# IMU_PCB.net
KiCad netlist of a schematic drawn in EAGLE
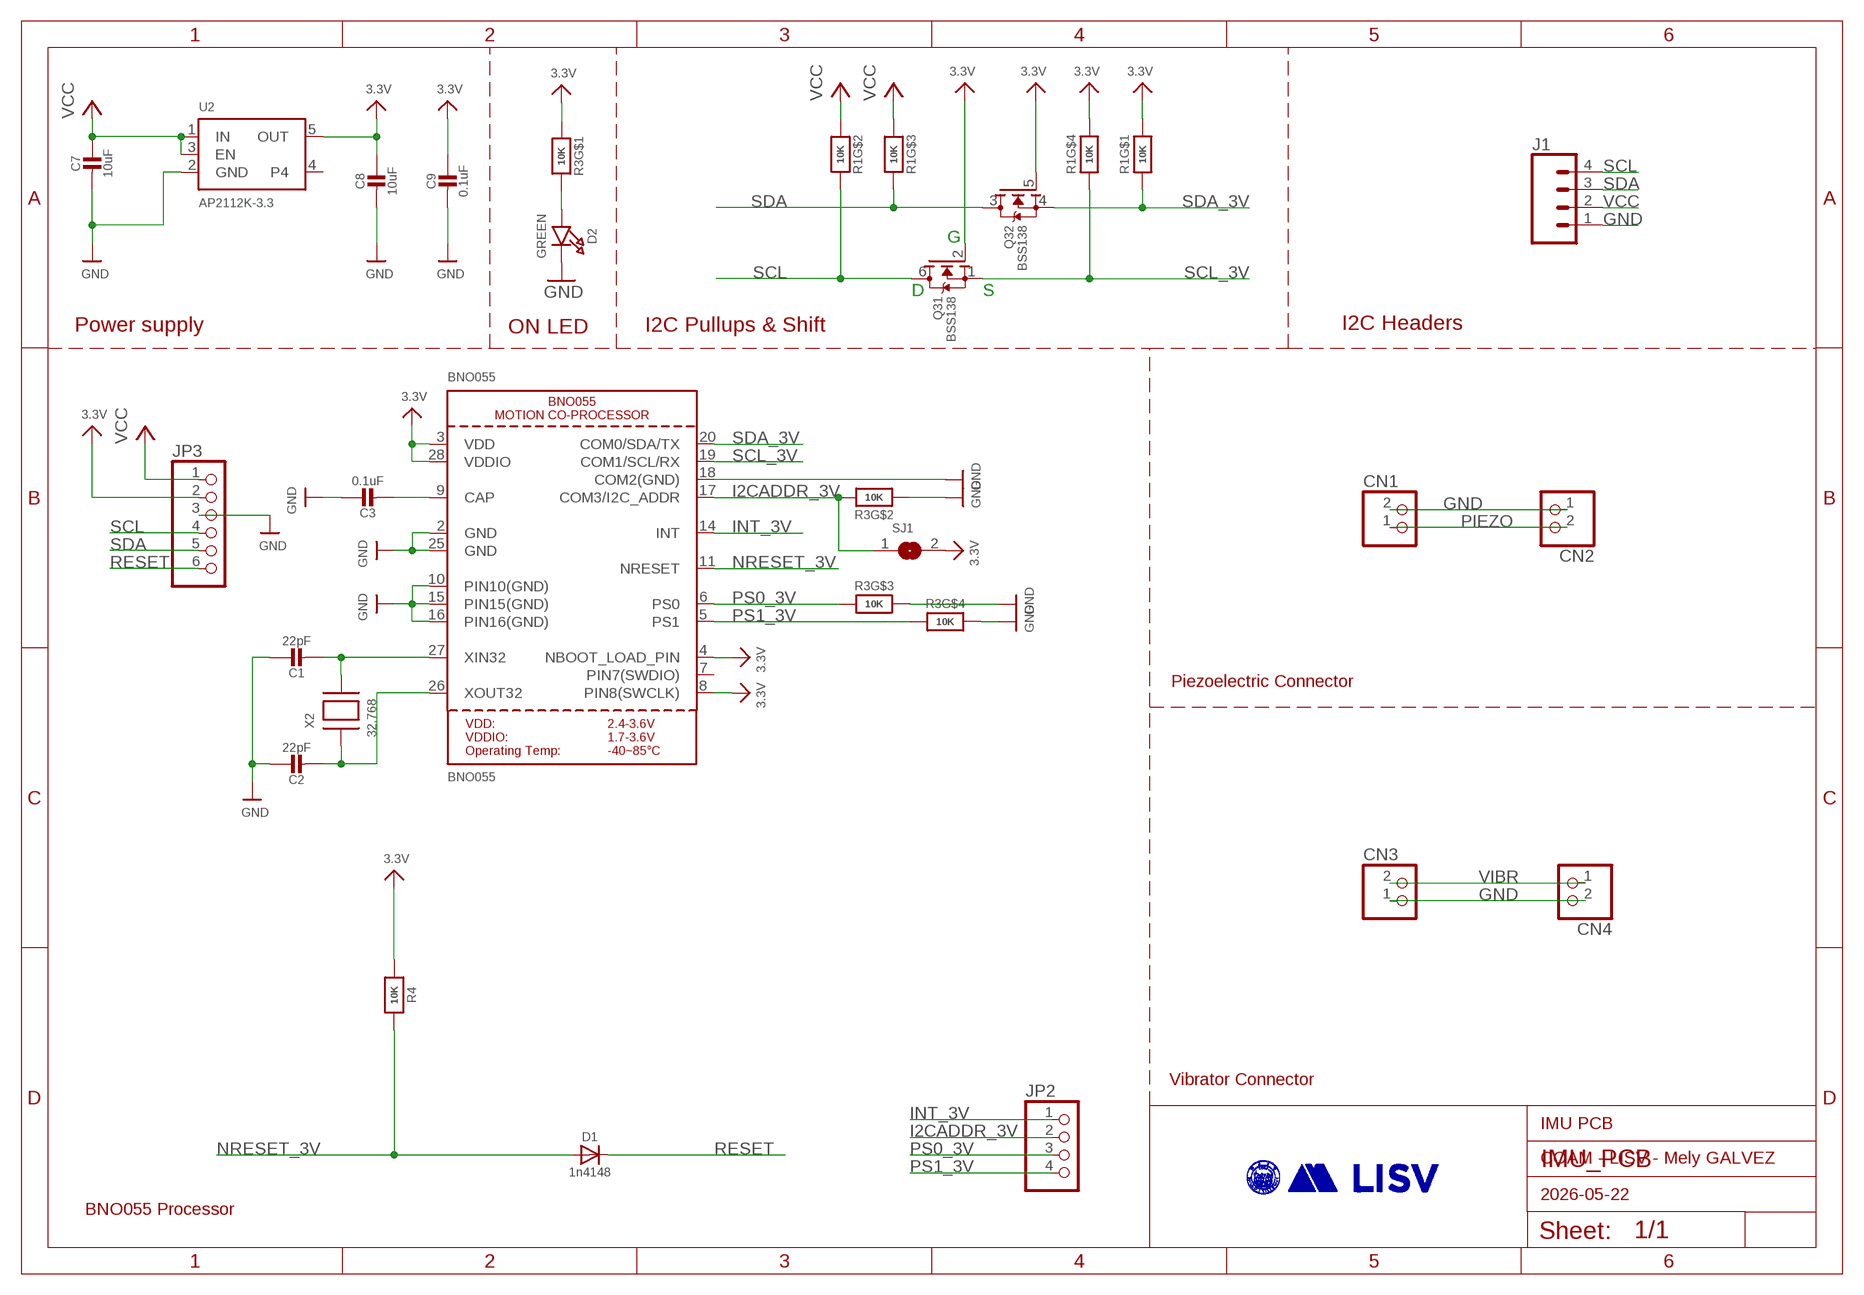
[diagram p0: schematic, sheet 1]

(export (version "E")
  (design (tool "Eeschema 10.0.6"))
  (components
    (comp (ref "BNO055")
      (value "BNO055")
      (footprint "eagle-import:BNO055")
      (libsource (lib "eagle-import") (part "BNO055"))
    )
    (comp (ref "C1")
      (value "22pF")
      (footprint "eagle-import:0603-NO")
      (libsource (lib "eagle-import") (part "CAP_CERAMIC0603_NO"))
    )
    (comp (ref "C2")
      (value "22pF")
      (footprint "eagle-import:0603-NO")
      (libsource (lib "eagle-import") (part "CAP_CERAMIC0603_NO"))
    )
    (comp (ref "C3")
      (value "0.1uF")
      (footprint "eagle-import:0603-NO")
      (libsource (lib "eagle-import") (part "CAP_CERAMIC0603_NO"))
    )
    (comp (ref "C7")
      (value "10uF")
      (footprint "eagle-import:0805-NO")
      (libsource (lib "eagle-import") (part "CAP_CERAMIC0805-NOOUTLINE"))
    )
    (comp (ref "C8")
      (value "10uF")
      (footprint "eagle-import:0805-NO")
      (libsource (lib "eagle-import") (part "CAP_CERAMIC0805-NOOUTLINE"))
    )
    (comp (ref "C9")
      (value "0.1uF")
      (footprint "eagle-import:0603-NO")
      (libsource (lib "eagle-import") (part "CAP_CERAMIC0603_NO"))
    )
    (comp (ref "CN1")
      (value "JST_2PIN-SMT-RA")
      (footprint "eagle-import:JST-PH-2-SMT-RA")
      (libsource (lib "eagle-import") (part "JST_2PIN-SMT-RA"))
    )
    (comp (ref "CN2")
      (value "JST_2PIN-SMT-RA")
      (footprint "eagle-import:JST-PH-2-SMT-RA")
      (libsource (lib "eagle-import") (part "JST_2PIN-SMT-RA"))
    )
    (comp (ref "CN3")
      (value "JST_2PIN-SMT-RA")
      (footprint "eagle-import:JST-PH-2-SMT-RA")
      (libsource (lib "eagle-import") (part "JST_2PIN-SMT-RA"))
    )
    (comp (ref "CN4")
      (value "JST_2PIN-SMT-RA")
      (footprint "eagle-import:JST-PH-2-SMT-RA")
      (libsource (lib "eagle-import") (part "JST_2PIN-SMT-RA"))
    )
    (comp (ref "D1")
      (value "1n4148")
      (footprint "eagle-import:SOD-323")
      (libsource (lib "eagle-import") (part "DIODESOD-323"))
    )
    (comp (ref "D2")
      (value "GREEN")
      (footprint "eagle-import:CHIPLED_0603_NOOUTLINE")
      (libsource (lib "eagle-import") (part "LED0603_NOOUTLINE"))
    )
    (comp (ref "J1")
      (value "CONN_04JST-SMD-LOCKING")
      (footprint "eagle-import:JST-4-SMD-1.25MM-LOCKING")
      (libsource (lib "eagle-import") (part "CONN_04JST-SMD-LOCKING"))
    )
    (comp (ref "JP2")
      (value "HEADER-1X476MIL")
      (footprint "eagle-import:1X04_ROUND_76")
      (libsource (lib "eagle-import") (part "HEADER-1X476MIL"))
    )
    (comp (ref "JP3")
      (value "HEADER-1X670MIL")
      (footprint "eagle-import:1X06_ROUND_70")
      (libsource (lib "eagle-import") (part "HEADER-1X670MIL"))
    )
    (comp (ref "Q3")
      (value "BSS138")
      (footprint "eagle-import:SOT363")
      (libsource (lib "eagle-import") (part "MOSFET-N_DUAL"))
    )
    (comp (ref "R1")
      (value "10K")
      (footprint "eagle-import:RESPACK_4X0603")
      (libsource (lib "eagle-import") (part "RESISTOR_4PACK"))
    )
    (comp (ref "R3")
      (value "10K")
      (footprint "eagle-import:RESPACK_4X0603")
      (libsource (lib "eagle-import") (part "RESISTOR_4PACK"))
    )
    (comp (ref "R4")
      (value "10K")
      (footprint "eagle-import:0603-NO")
      (libsource (lib "eagle-import") (part "RESISTOR_0603_NOOUT"))
    )
    (comp (ref "SJ1")
      (value "SOLDERJUMPER")
      (footprint "eagle-import:SOLDERJUMPER_ARROW_NOPASTE")
      (libsource (lib "eagle-import") (part "SOLDERJUMPER"))
    )
    (comp (ref "U2")
      (value "AP2112K-3.3")
      (footprint "eagle-import:SOT23-5")
      (libsource (lib "eagle-import") (part "VREG_SOT23-5"))
    )
    (comp (ref "X2")
      (value "32.768")
      (footprint "eagle-import:XTAL3215")
      (libsource (lib "eagle-import") (part "XTAL-3.2X1.5"))
    )
  )
  (nets
    (net (code "1") (name "/I2CADDR_3V") (class "Default")
      (node (ref "BNO055") (pin "17") (pinfunction "COM3/I2C_ADDR_17") (pintype "bidirectional"))
      (node (ref "JP2") (pin "2") (pinfunction "2_2") (pintype "passive"))
      (node (ref "R3") (pin "7") (pinfunction "2_7") (pintype "passive"))
      (node (ref "SJ1") (pin "1") (pinfunction "1_1") (pintype "passive"))
    )
    (net (code "2") (name "/INT_3V") (class "Default")
      (node (ref "BNO055") (pin "14") (pinfunction "INT_14") (pintype "output"))
      (node (ref "JP2") (pin "1") (pinfunction "1_1") (pintype "passive"))
    )
    (net (code "3") (name "/NRESET_3V") (class "Default")
      (node (ref "BNO055") (pin "11") (pinfunction "NRESET_11") (pintype "bidirectional"))
      (node (ref "D1") (pin "A") (pinfunction "A_A") (pintype "passive"))
      (node (ref "R4") (pin "2") (pinfunction "2_2") (pintype "passive"))
    )
    (net (code "4") (name "/PIEZO") (class "Default")
      (node (ref "CN1") (pin "1") (pinfunction "2_1") (pintype "passive"))
      (node (ref "CN2") (pin "2") (pinfunction "1_2") (pintype "passive"))
    )
    (net (code "5") (name "/PS0_3V") (class "Default")
      (node (ref "BNO055") (pin "6") (pinfunction "PS0_6") (pintype "input"))
      (node (ref "JP2") (pin "3") (pinfunction "3_3") (pintype "passive"))
      (node (ref "R3") (pin "3") (pinfunction "1_3") (pintype "passive"))
    )
    (net (code "6") (name "/PS1_3V") (class "Default")
      (node (ref "BNO055") (pin "5") (pinfunction "PS1_5") (pintype "input"))
      (node (ref "JP2") (pin "4") (pinfunction "4_4") (pintype "passive"))
      (node (ref "R3") (pin "4") (pinfunction "1_4") (pintype "passive"))
    )
    (net (code "7") (name "/RESET") (class "Default")
      (node (ref "D1") (pin "C") (pinfunction "C_C") (pintype "passive"))
      (node (ref "JP3") (pin "6") (pinfunction "6_6") (pintype "passive"))
    )
    (net (code "8") (name "/SCL") (class "Default")
      (node (ref "J1") (pin "4") (pinfunction "4_4") (pintype "passive"))
      (node (ref "JP3") (pin "4") (pinfunction "4_4") (pintype "passive"))
      (node (ref "Q3") (pin "6") (pinfunction "D_6") (pintype "bidirectional"))
      (node (ref "R1") (pin "7") (pinfunction "2_7") (pintype "passive"))
    )
    (net (code "9") (name "/SCL_3V") (class "Default")
      (node (ref "BNO055") (pin "19") (pinfunction "COM1/SCL/RX_19") (pintype "bidirectional"))
      (node (ref "Q3") (pin "1") (pinfunction "S_1") (pintype "bidirectional"))
      (node (ref "R1") (pin "5") (pinfunction "2_5") (pintype "passive"))
    )
    (net (code "10") (name "/SDA") (class "Default")
      (node (ref "J1") (pin "3") (pinfunction "3_3") (pintype "passive"))
      (node (ref "JP3") (pin "5") (pinfunction "5_5") (pintype "passive"))
      (node (ref "Q3") (pin "3") (pinfunction "D_3") (pintype "bidirectional"))
      (node (ref "R1") (pin "6") (pinfunction "2_6") (pintype "passive"))
    )
    (net (code "11") (name "/SDA_3V") (class "Default")
      (node (ref "BNO055") (pin "20") (pinfunction "COM0/SDA/TX_20") (pintype "bidirectional"))
      (node (ref "Q3") (pin "4") (pinfunction "S_4") (pintype "bidirectional"))
      (node (ref "R1") (pin "8") (pinfunction "2_8") (pintype "passive"))
    )
    (net (code "12") (name "/VIBR") (class "Default")
      (node (ref "CN3") (pin "2") (pinfunction "1_2") (pintype "passive"))
      (node (ref "CN4") (pin "1") (pinfunction "2_1") (pintype "passive"))
    )
    (net (code "13") (name "3.3V") (class "Default")
      (node (ref "BNO055") (pin "28") (pinfunction "VDDIO_28") (pintype "power_in"))
      (node (ref "BNO055") (pin "3") (pinfunction "VDD_3") (pintype "power_in"))
      (node (ref "BNO055") (pin "4") (pinfunction "NBOOT_LOAD_PIN_4") (pintype "bidirectional"))
      (node (ref "BNO055") (pin "8") (pinfunction "PIN8(SWCLK)_8") (pintype "bidirectional"))
      (node (ref "C8") (pin "1") (pinfunction "1_1") (pintype "passive"))
      (node (ref "C9") (pin "1") (pinfunction "1_1") (pintype "passive"))
      (node (ref "JP3") (pin "2") (pinfunction "2_2") (pintype "passive"))
      (node (ref "Q3") (pin "2") (pinfunction "G_2") (pintype "bidirectional"))
      (node (ref "Q3") (pin "5") (pinfunction "G_5") (pintype "bidirectional"))
      (node (ref "R1") (pin "1") (pinfunction "1_1") (pintype "passive"))
      (node (ref "R1") (pin "4") (pinfunction "1_4") (pintype "passive"))
      (node (ref "R3") (pin "1") (pinfunction "1_1") (pintype "passive"))
      (node (ref "R4") (pin "1") (pinfunction "1_1") (pintype "passive"))
      (node (ref "SJ1") (pin "2") (pinfunction "2_2") (pintype "passive"))
      (node (ref "U2") (pin "5") (pinfunction "OUT_5") (pintype "power_in"))
    )
    (net (code "14") (name "GND") (class "Default")
      (node (ref "BNO055") (pin "10") (pinfunction "PIN10(GND)_10") (pintype "bidirectional"))
      (node (ref "BNO055") (pin "15") (pinfunction "PIN15(GND)_15") (pintype "bidirectional"))
      (node (ref "BNO055") (pin "16") (pinfunction "PIN16(GND)_16") (pintype "bidirectional"))
      (node (ref "BNO055") (pin "18") (pinfunction "COM2(GND)_18") (pintype "bidirectional"))
      (node (ref "BNO055") (pin "2") (pinfunction "GND_2") (pintype "power_in"))
      (node (ref "BNO055") (pin "25") (pinfunction "GND_25") (pintype "power_in"))
      (node (ref "C1") (pin "1") (pinfunction "1_1") (pintype "passive"))
      (node (ref "C2") (pin "1") (pinfunction "1_1") (pintype "passive"))
      (node (ref "C3") (pin "1") (pinfunction "1_1") (pintype "passive"))
      (node (ref "C7") (pin "2") (pinfunction "2_2") (pintype "passive"))
      (node (ref "C8") (pin "2") (pinfunction "2_2") (pintype "passive"))
      (node (ref "C9") (pin "2") (pinfunction "2_2") (pintype "passive"))
      (node (ref "CN1") (pin "2") (pinfunction "1_2") (pintype "passive"))
      (node (ref "CN2") (pin "1") (pinfunction "2_1") (pintype "passive"))
      (node (ref "CN3") (pin "1") (pinfunction "2_1") (pintype "passive"))
      (node (ref "CN4") (pin "2") (pinfunction "1_2") (pintype "passive"))
      (node (ref "D2") (pin "C") (pinfunction "C_C") (pintype "passive"))
      (node (ref "J1") (pin "1") (pinfunction "1_1") (pintype "passive"))
      (node (ref "JP3") (pin "3") (pinfunction "3_3") (pintype "passive"))
      (node (ref "R3") (pin "2") (pinfunction "1_2") (pintype "passive"))
      (node (ref "R3") (pin "5") (pinfunction "2_5") (pintype "passive"))
      (node (ref "R3") (pin "6") (pinfunction "2_6") (pintype "passive"))
      (node (ref "U2") (pin "2") (pinfunction "GND_2") (pintype "power_in"))
    )
    (net (code "15") (name "Net-(BNO055-CAP)") (class "Default")
      (node (ref "BNO055") (pin "9") (pinfunction "CAP_9") (pintype "passive"))
      (node (ref "C3") (pin "2") (pinfunction "2_2") (pintype "passive"))
    )
    (net (code "16") (name "Net-(BNO055-XIN32)") (class "Default")
      (node (ref "BNO055") (pin "27") (pinfunction "XIN32_27") (pintype "input"))
      (node (ref "C1") (pin "2") (pinfunction "2_2") (pintype "passive"))
      (node (ref "X2") (pin "P$2") (pinfunction "P$2_P$2") (pintype "bidirectional"))
    )
    (net (code "17") (name "Net-(BNO055-XOUT32)") (class "Default")
      (node (ref "BNO055") (pin "26") (pinfunction "XOUT32_26") (pintype "output"))
      (node (ref "C2") (pin "2") (pinfunction "2_2") (pintype "passive"))
      (node (ref "X2") (pin "P$1") (pinfunction "P$1_P$1") (pintype "bidirectional"))
    )
    (net (code "18") (name "Net-(R3A-2)") (class "Default")
      (node (ref "D2") (pin "A") (pinfunction "A_A") (pintype "passive"))
      (node (ref "R3") (pin "8") (pinfunction "2_8") (pintype "passive"))
    )
    (net (code "19") (name "VCC") (class "Default")
      (node (ref "C7") (pin "1") (pinfunction "1_1") (pintype "passive"))
      (node (ref "J1") (pin "2") (pinfunction "2_2") (pintype "passive"))
      (node (ref "JP3") (pin "1") (pinfunction "1_1") (pintype "passive"))
      (node (ref "R1") (pin "2") (pinfunction "1_2") (pintype "passive"))
      (node (ref "R1") (pin "3") (pinfunction "1_3") (pintype "passive"))
      (node (ref "U2") (pin "1") (pinfunction "IN_1") (pintype "power_in"))
      (node (ref "U2") (pin "3") (pinfunction "EN_3") (pintype "input"))
    )
    (net (code "20") (name "unconnected-(BNO055-PIN7(SWDIO)-Pad7)") (class "Default")
      (node (ref "BNO055") (pin "7") (pinfunction "PIN7(SWDIO)_7") (pintype "bidirectional"))
    )
    (net (code "21") (name "unconnected-(U2-P4-Pad4)") (class "Default")
      (node (ref "U2") (pin "4") (pinfunction "P4_4") (pintype "bidirectional"))
    )
  )
)
